# 14.net
KiCad netlist of a schematic drawn in EasyEDA Pro
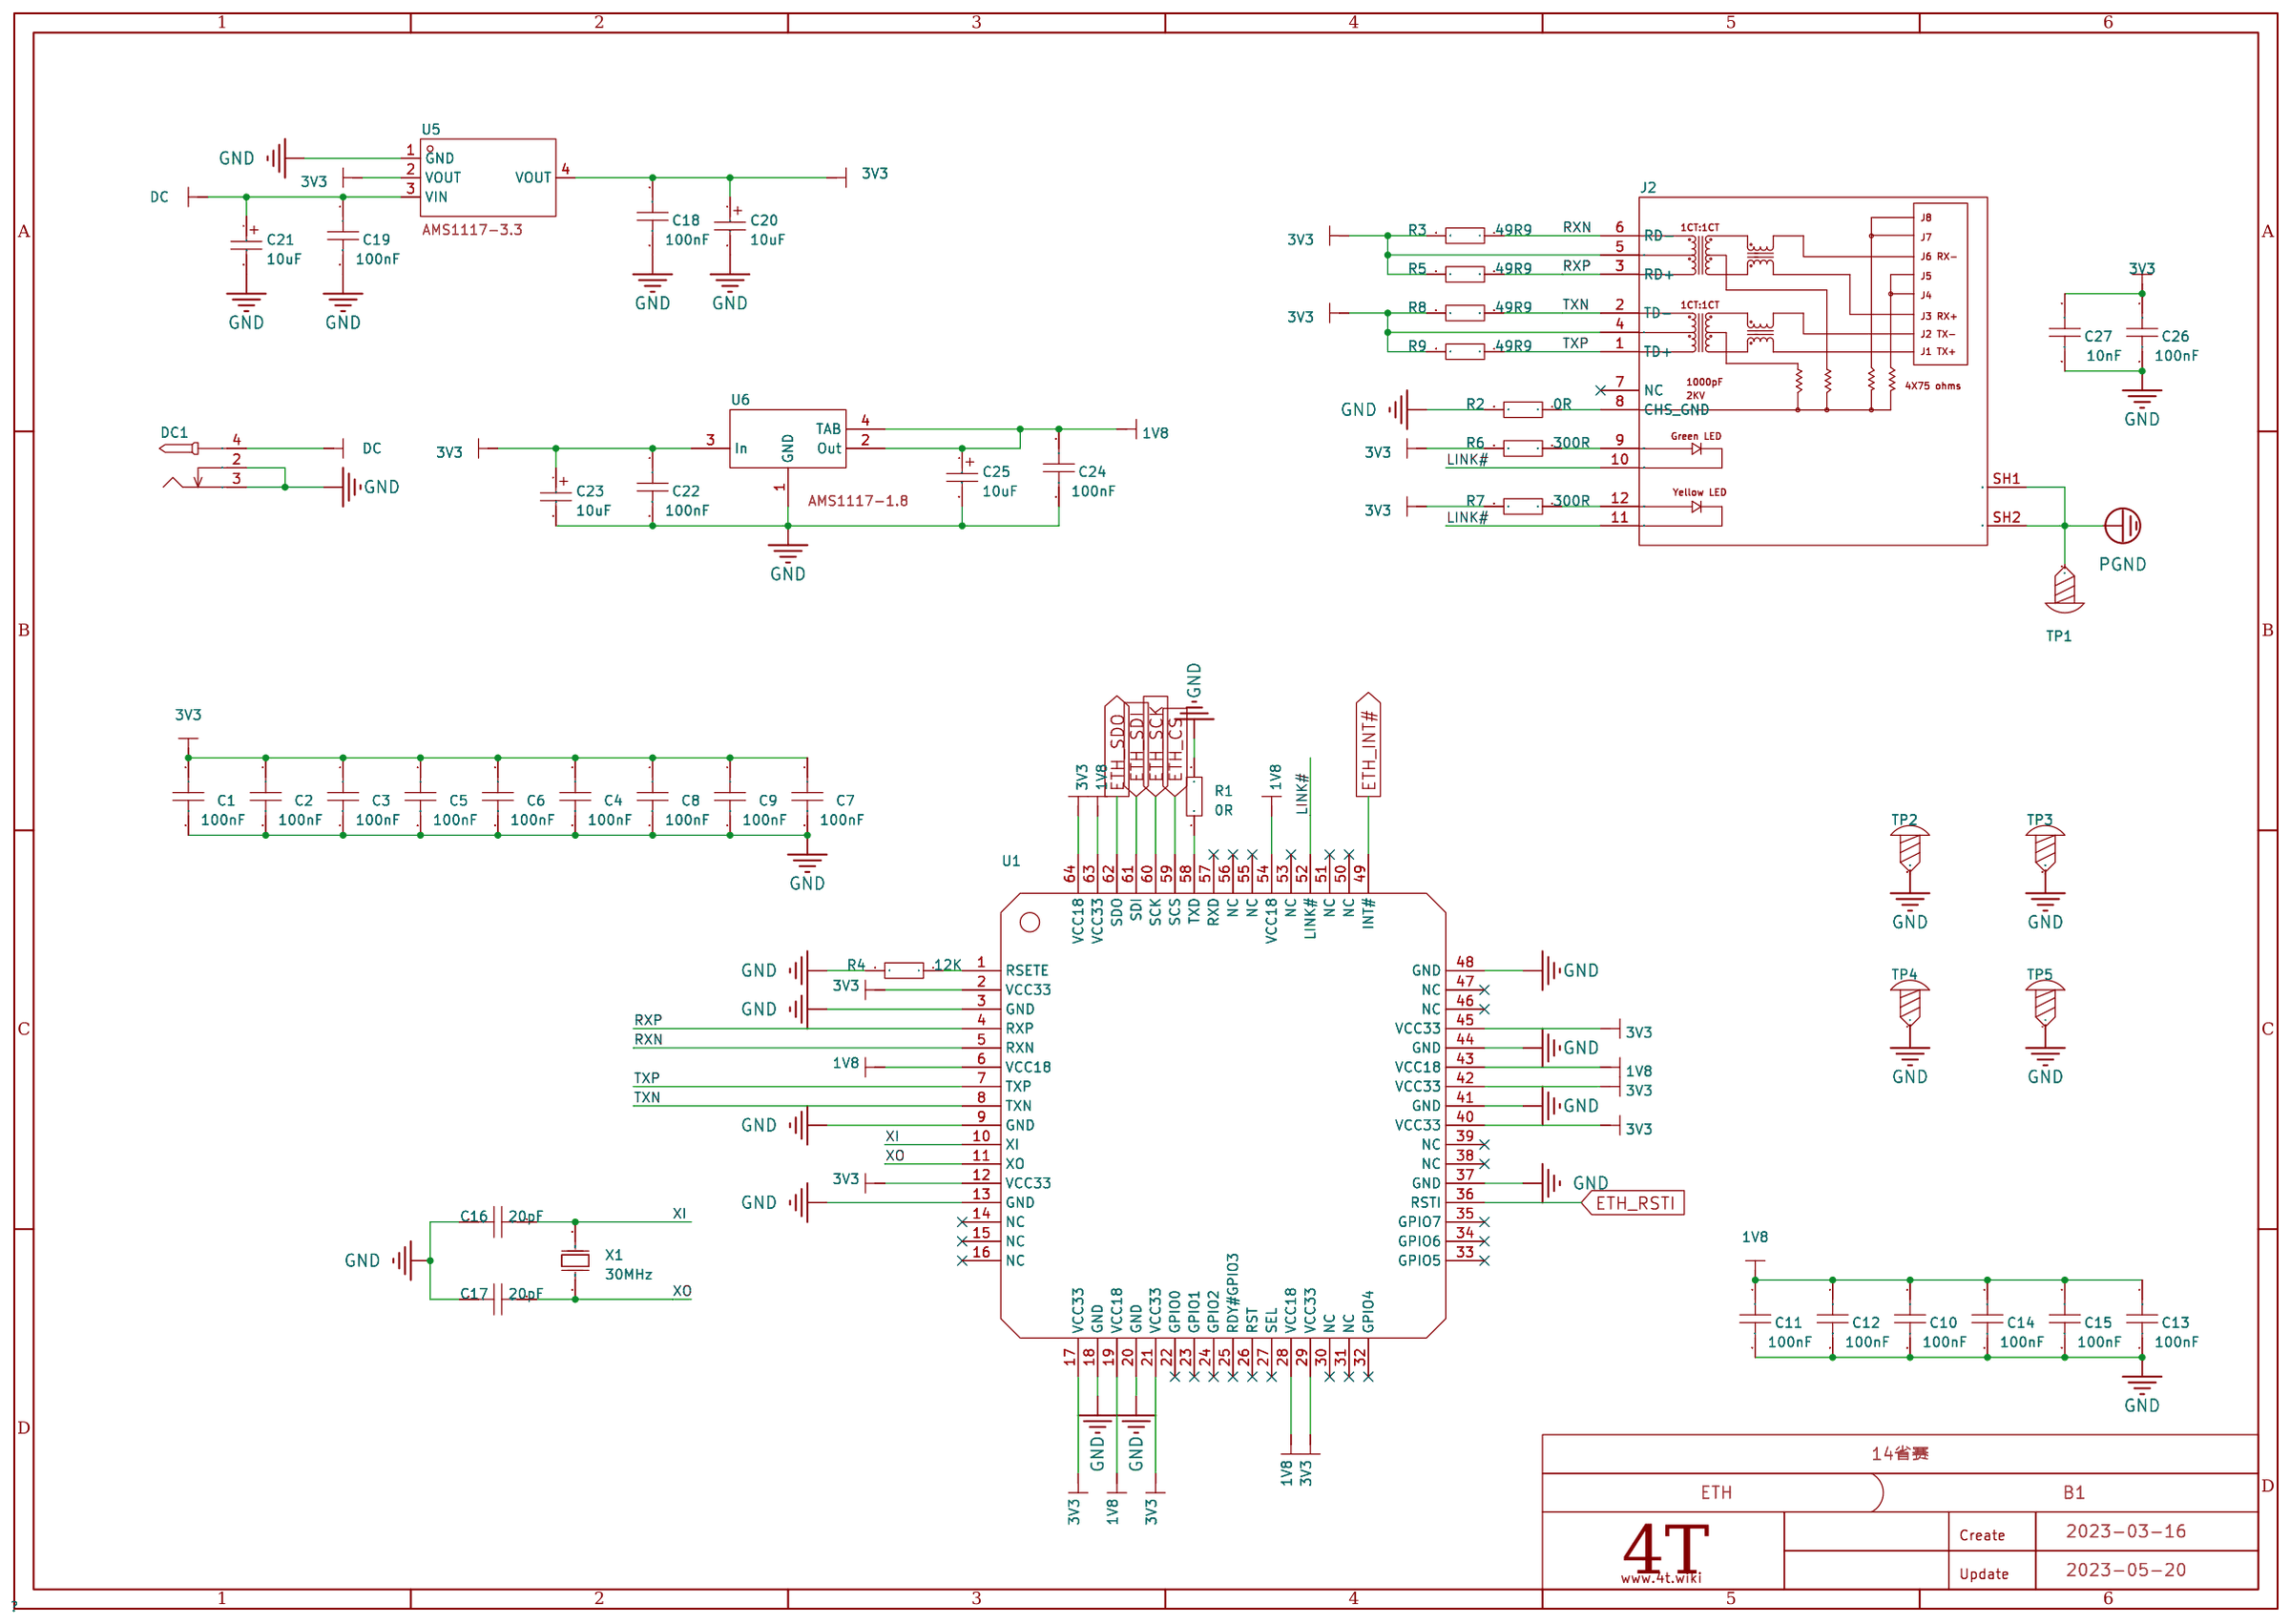
[diagram p0: ETH]
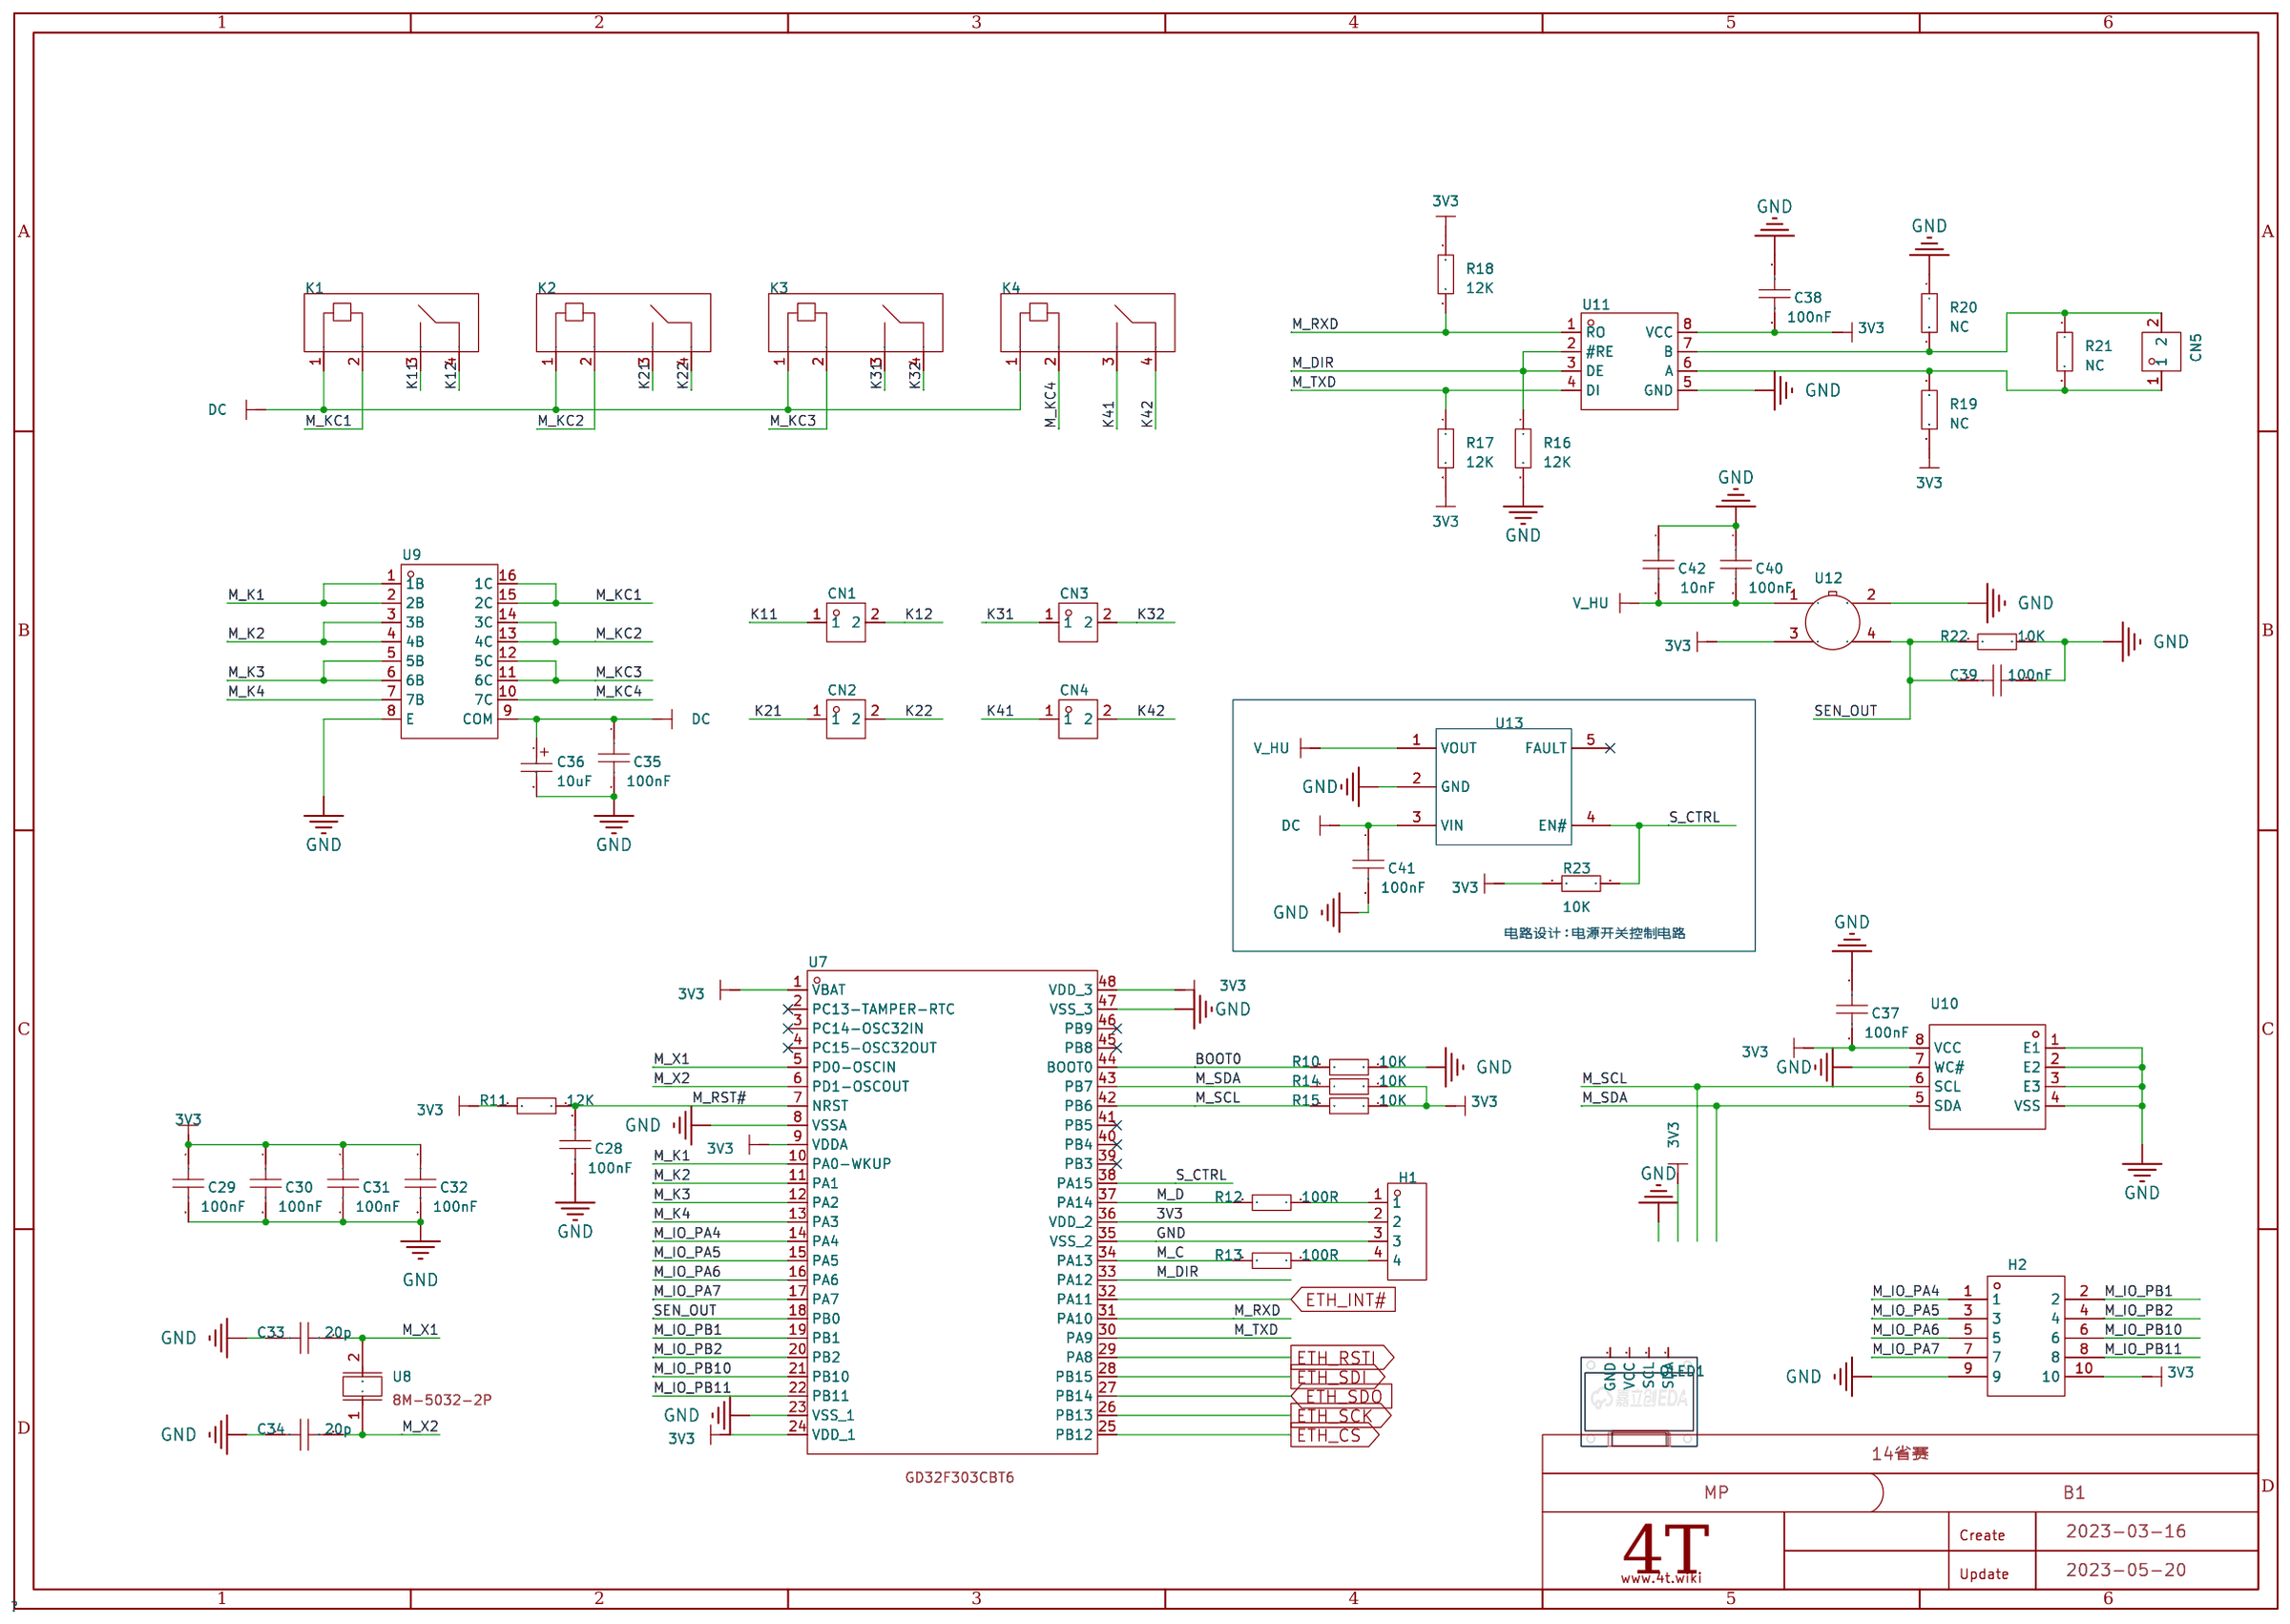
[diagram p1: MP]

(export (version "E")
  (design (tool "Eeschema 10.0.6"))
  (components
    (comp (ref "C1")
      (value "100nF")
      (footprint "easyedapro:C0805")
      (libsource (lib "easyedapro") (part "CapAcitance"))
    )
    (comp (ref "C2")
      (value "100nF")
      (footprint "easyedapro:C0805")
      (libsource (lib "easyedapro") (part "CapAcitance"))
    )
    (comp (ref "C3")
      (value "100nF")
      (footprint "easyedapro:C0805")
      (libsource (lib "easyedapro") (part "CapAcitance"))
    )
    (comp (ref "C4")
      (value "100nF")
      (footprint "easyedapro:C0805")
      (libsource (lib "easyedapro") (part "CapAcitance"))
    )
    (comp (ref "C5")
      (value "100nF")
      (footprint "easyedapro:C0805")
      (libsource (lib "easyedapro") (part "CapAcitance"))
    )
    (comp (ref "C6")
      (value "100nF")
      (footprint "easyedapro:C0805")
      (libsource (lib "easyedapro") (part "CapAcitance"))
    )
    (comp (ref "C7")
      (value "100nF")
      (footprint "easyedapro:C0805")
      (libsource (lib "easyedapro") (part "CapAcitance"))
    )
    (comp (ref "C8")
      (value "100nF")
      (footprint "easyedapro:C0805")
      (libsource (lib "easyedapro") (part "CapAcitance"))
    )
    (comp (ref "C9")
      (value "100nF")
      (footprint "easyedapro:C0805")
      (libsource (lib "easyedapro") (part "CapAcitance"))
    )
    (comp (ref "C10")
      (value "100nF")
      (footprint "easyedapro:C0805")
      (libsource (lib "easyedapro") (part "CapAcitance"))
    )
    (comp (ref "C11")
      (value "100nF")
      (footprint "easyedapro:C0805")
      (libsource (lib "easyedapro") (part "CapAcitance"))
    )
    (comp (ref "C12")
      (value "100nF")
      (footprint "easyedapro:C0805")
      (libsource (lib "easyedapro") (part "CapAcitance"))
    )
    (comp (ref "C13")
      (value "100nF")
      (footprint "easyedapro:C0805")
      (libsource (lib "easyedapro") (part "CapAcitance"))
    )
    (comp (ref "C14")
      (value "100nF")
      (footprint "easyedapro:C0805")
      (libsource (lib "easyedapro") (part "CapAcitance"))
    )
    (comp (ref "C15")
      (value "100nF")
      (footprint "easyedapro:C0805")
      (libsource (lib "easyedapro") (part "CapAcitance"))
    )
    (comp (ref "C16")
      (value "20pF")
      (footprint "easyedapro:C0805")
      (libsource (lib "easyedapro") (part "CapAcitance"))
    )
    (comp (ref "C17")
      (value "20pF")
      (footprint "easyedapro:C0805")
      (libsource (lib "easyedapro") (part "CapAcitance"))
    )
    (comp (ref "C18")
      (value "100nF")
      (footprint "easyedapro:C0805")
      (libsource (lib "easyedapro") (part "CapAcitance"))
    )
    (comp (ref "C19")
      (value "100nF")
      (footprint "easyedapro:C0805")
      (libsource (lib "easyedapro") (part "CapAcitance"))
    )
    (comp (ref "C20")
      (value "10uF")
      (footprint "easyedapro:C_Ele_SMD_3x5.4mm")
      (libsource (lib "easyedapro") (part "CAP"))
    )
    (comp (ref "C21")
      (value "10uF")
      (footprint "easyedapro:C_Ele_SMD_3x5.4mm")
      (libsource (lib "easyedapro") (part "CAP"))
    )
    (comp (ref "C22")
      (value "100nF")
      (footprint "easyedapro:C0805")
      (libsource (lib "easyedapro") (part "CapAcitance"))
    )
    (comp (ref "C23")
      (value "10uF")
      (footprint "easyedapro:C_Ele_SMD_3x5.4mm")
      (libsource (lib "easyedapro") (part "CAP"))
    )
    (comp (ref "C24")
      (value "100nF")
      (footprint "easyedapro:C0805")
      (libsource (lib "easyedapro") (part "CapAcitance"))
    )
    (comp (ref "C25")
      (value "10uF")
      (footprint "easyedapro:C_Ele_SMD_3x5.4mm")
      (libsource (lib "easyedapro") (part "CAP"))
    )
    (comp (ref "C26")
      (value "100nF")
      (footprint "easyedapro:C0805")
      (libsource (lib "easyedapro") (part "CapAcitance"))
    )
    (comp (ref "C27")
      (value "10nF")
      (footprint "easyedapro:C0805")
      (libsource (lib "easyedapro") (part "CapAcitance"))
    )
    (comp (ref "DC1")
      (value "~")
      (footprint "easyedapro:DC-2.0")
      (libsource (lib "easyedapro") (part "DC电源接口"))
    )
    (comp (ref "J2")
      (value "HY911105AE")
      (footprint "easyedapro:RJ45-TH_HR911105A")
      (description "连接器类型:RJ插座;USOC代码:RJ45;端口数量:1;等级:-;屏蔽:-;LED:-;")
      (fields (field (name "Manufacturer") "HANRUN(汉仁)"))
      (libsource (lib "easyedapro") (part "HY911105AE"))
    )
    (comp (ref "R1") (value "0R") (footprint "easyedapro:R0805") (libsource (lib "easyedapro") (part "电阻")))
    (comp (ref "R2") (value "0R") (footprint "easyedapro:R0805") (libsource (lib "easyedapro") (part "电阻")))
    (comp (ref "R3") (value "49R9") (footprint "easyedapro:R0805") (libsource (lib "easyedapro") (part "电阻")))
    (comp (ref "R4") (value "12K") (footprint "easyedapro:R0805") (libsource (lib "easyedapro") (part "电阻")))
    (comp (ref "R5") (value "49R9") (footprint "easyedapro:R0805") (libsource (lib "easyedapro") (part "电阻")))
    (comp (ref "R6") (value "300R") (footprint "easyedapro:R0805") (libsource (lib "easyedapro") (part "电阻")))
    (comp (ref "R7") (value "300R") (footprint "easyedapro:R0805") (libsource (lib "easyedapro") (part "电阻")))
    (comp (ref "R8") (value "49R9") (footprint "easyedapro:R0805") (libsource (lib "easyedapro") (part "电阻")))
    (comp (ref "R9") (value "49R9") (footprint "easyedapro:R0805") (libsource (lib "easyedapro") (part "电阻")))
    (comp (ref "TP1") (value "~") (footprint "easyedapro:M2螺丝") (libsource (lib "easyedapro") (part "螺丝孔")))
    (comp (ref "TP2") (value "~") (footprint "easyedapro:M2螺丝") (libsource (lib "easyedapro") (part "螺丝孔")))
    (comp (ref "TP3") (value "~") (footprint "easyedapro:M2螺丝") (libsource (lib "easyedapro") (part "螺丝孔")))
    (comp (ref "TP4") (value "~") (footprint "easyedapro:M2螺丝") (libsource (lib "easyedapro") (part "螺丝孔")))
    (comp (ref "TP5") (value "~") (footprint "easyedapro:M2螺丝") (libsource (lib "easyedapro") (part "螺丝孔")))
    (comp (ref "U1")
      (value "CH395Q")
      (footprint "easyedapro:LQFP-64_L10.0-W10.0-P0.50-LS12.0-BL")
      (description "应用功能:以太网控制器;通道数:-;接口类型:Parallel, SPI, UART;电源电压:1.65V~3.6V;电源电流:90mA;")
      (fields (field (name "Manufacturer") "WCH(南京沁恒)"))
      (libsource (lib "easyedapro") (part "CH395Q"))
    )
    (comp (ref "U5")
      (value "AMS1117-3.3")
      (footprint "easyedapro:SOT-223-3_L6.5-W3.4-P2.30-LS7.0-BR")
      (fields (field (name "Manufacturer Part") "AMS1117-3.3") (field (name "Manufacturer") "AMS"))
      (libsource (lib "easyedapro") (part "AMS1117-3.3"))
    )
    (comp (ref "U6")
      (value "AMS1117-1.8")
      (footprint "easyedapro:SOT-223-4_L6.5-W3.5-P2.30-LS7.0-BR")
      (description "输出类型:固定;输出极性:正;输出通道数:1;最大输入电压:15V;输出电压:1.8V~1.8V;压差:1.3V@(1A);输出电流:1A;电源纹波抑制比(PSRR):75dB@(120Hz);")
      (fields (field (name "Manufacturer Part") "AMS1117-1.8") (field (name "Manufacturer") "AMS"))
      (libsource (lib "easyedapro") (part "AMS1117-1.8"))
    )
    (comp (ref "X1")
      (value "30MHz")
      (footprint "easyedapro:OSC-SMD_L5.0-W3.2")
      (description "晶振类型:贴片无源晶振;频率:30MHz;频率公差:±10ppm;频率稳定度:±50ppm;负载电容:20pF;工作温度:-40°C~+85°C;")
      (fields (field (name "Manufacturer Part") "X503230MSB2GI") (field (name "Manufacturer") "YXC(扬兴晶振)"))
      (libsource (lib "easyedapro") (part "X503230MSB2GI"))
    )
    (comp (ref "C28")
      (value "100nF")
      (footprint "easyedapro:C0805")
      (libsource (lib "easyedapro") (part "CapAcitance"))
    )
    (comp (ref "C29")
      (value "100nF")
      (footprint "easyedapro:C0805")
      (libsource (lib "easyedapro") (part "CapAcitance"))
    )
    (comp (ref "C30")
      (value "100nF")
      (footprint "easyedapro:C0805")
      (libsource (lib "easyedapro") (part "CapAcitance"))
    )
    (comp (ref "C31")
      (value "100nF")
      (footprint "easyedapro:C0805")
      (libsource (lib "easyedapro") (part "CapAcitance"))
    )
    (comp (ref "C32")
      (value "100nF")
      (footprint "easyedapro:C0805")
      (libsource (lib "easyedapro") (part "CapAcitance"))
    )
    (comp (ref "C33")
      (value "20p")
      (footprint "easyedapro:C0805")
      (libsource (lib "easyedapro") (part "CapAcitance"))
    )
    (comp (ref "C34")
      (value "20p")
      (footprint "easyedapro:C0805")
      (libsource (lib "easyedapro") (part "CapAcitance"))
    )
    (comp (ref "C35")
      (value "100nF")
      (footprint "easyedapro:C0805")
      (libsource (lib "easyedapro") (part "CapAcitance"))
    )
    (comp (ref "C36")
      (value "10uF")
      (footprint "easyedapro:C_Ele_SMD_3x5.4mm")
      (libsource (lib "easyedapro") (part "CAP"))
    )
    (comp (ref "C37")
      (value "100nF")
      (footprint "easyedapro:C0805")
      (libsource (lib "easyedapro") (part "CapAcitance"))
    )
    (comp (ref "C38")
      (value "100nF")
      (footprint "easyedapro:C0805")
      (libsource (lib "easyedapro") (part "CapAcitance"))
    )
    (comp (ref "C39")
      (value "100nF")
      (footprint "easyedapro:C0805")
      (libsource (lib "easyedapro") (part "CapAcitance"))
    )
    (comp (ref "C40")
      (value "100nF")
      (footprint "easyedapro:C0805")
      (libsource (lib "easyedapro") (part "CapAcitance"))
    )
    (comp (ref "C41")
      (value "100nF")
      (footprint "easyedapro:C0805")
      (libsource (lib "easyedapro") (part "CapAcitance"))
    )
    (comp (ref "C42")
      (value "10nF")
      (footprint "easyedapro:C0805")
      (libsource (lib "easyedapro") (part "CapAcitance"))
    )
    (comp (ref "CN1")
      (value "KF128L-5.08-2P 蓝色")
      (footprint "easyedapro:TH_KF128L-5.08-2P")
      (libsource (lib "easyedapro") (part "KF128L-5.08-2P 蓝色"))
    )
    (comp (ref "CN2")
      (value "KF128L-5.08-2P 蓝色")
      (footprint "easyedapro:TH_KF128L-5.08-2P")
      (libsource (lib "easyedapro") (part "KF128L-5.08-2P 蓝色"))
    )
    (comp (ref "CN3")
      (value "KF128L-5.08-2P 蓝色")
      (footprint "easyedapro:TH_KF128L-5.08-2P")
      (libsource (lib "easyedapro") (part "KF128L-5.08-2P 蓝色"))
    )
    (comp (ref "CN4")
      (value "KF128L-5.08-2P 蓝色")
      (footprint "easyedapro:TH_KF128L-5.08-2P")
      (libsource (lib "easyedapro") (part "KF128L-5.08-2P 蓝色"))
    )
    (comp (ref "CN5")
      (value "KF128L-5.08-2P 蓝色")
      (footprint "easyedapro:TH_KF128L-5.08-2P")
      (libsource (lib "easyedapro") (part "KF128L-5.08-2P 蓝色"))
    )
    (comp (ref "H1")
      (value "~")
      (footprint "easyedapro:HDR-TH_4P-P2.54-V-F")
      (libsource (lib "easyedapro") (part "2.54-1*4P母"))
    )
    (comp (ref "H2")
      (value "~")
      (footprint "easyedapro:HDR-TH_10P-P2.54-V-M-R2-C5-S2.54")
      (libsource (lib "easyedapro") (part "HDR-M-2.54_2x5"))
    )
    (comp (ref "K1")
      (value "HF49FD/012-1H12")
      (footprint "easyedapro:RELAY-TH_HF49FD-XXX-1H12-XXX")
      (description "线圈电压:12V;线圈类型:非极化-单线圈;触点形式:一组常开:1A(单刀单掷-常开);最大切换电流:5A;触点材料:AgNi;")
      (fields (field (name "Manufacturer") "HF(宏发)"))
      (libsource (lib "easyedapro") (part "HF49FD/012-1H12"))
    )
    (comp (ref "K2")
      (value "HF49FD/012-1H12")
      (footprint "easyedapro:RELAY-TH_HF49FD-XXX-1H12-XXX")
      (description "线圈电压:12V;线圈类型:非极化-单线圈;触点形式:一组常开:1A(单刀单掷-常开);最大切换电流:5A;触点材料:AgNi;")
      (fields (field (name "Manufacturer") "HF(宏发)"))
      (libsource (lib "easyedapro") (part "HF49FD/012-1H12"))
    )
    (comp (ref "K3")
      (value "HF49FD/012-1H12")
      (footprint "easyedapro:RELAY-TH_HF49FD-XXX-1H12-XXX")
      (description "线圈电压:12V;线圈类型:非极化-单线圈;触点形式:一组常开:1A(单刀单掷-常开);最大切换电流:5A;触点材料:AgNi;")
      (fields (field (name "Manufacturer") "HF(宏发)"))
      (libsource (lib "easyedapro") (part "HF49FD/012-1H12"))
    )
    (comp (ref "K4")
      (value "HF49FD/012-1H12")
      (footprint "easyedapro:RELAY-TH_HF49FD-XXX-1H12-XXX")
      (description "线圈电压:12V;线圈类型:非极化-单线圈;触点形式:一组常开:1A(单刀单掷-常开);最大切换电流:5A;触点材料:AgNi;")
      (fields (field (name "Manufacturer") "HF(宏发)"))
      (libsource (lib "easyedapro") (part "HF49FD/012-1H12"))
    )
    (comp (ref "OLED1")
      (value "~")
      (footprint "easyedapro:0.96OLED_4P")
      (libsource (lib "easyedapro") (part "0.96OLED模块_4P"))
    )
    (comp (ref "R10") (value "10K") (footprint "easyedapro:R0805") (libsource (lib "easyedapro") (part "电阻")))
    (comp (ref "R11") (value "12K") (footprint "easyedapro:R0805") (libsource (lib "easyedapro") (part "电阻")))
    (comp (ref "R12")
      (value "100R")
      (footprint "easyedapro:R0805")
      (libsource (lib "easyedapro") (part "电阻"))
    )
    (comp (ref "R13")
      (value "100R")
      (footprint "easyedapro:R0805")
      (libsource (lib "easyedapro") (part "电阻"))
    )
    (comp (ref "R14") (value "10K") (footprint "easyedapro:R0805") (libsource (lib "easyedapro") (part "电阻")))
    (comp (ref "R15") (value "10K") (footprint "easyedapro:R0805") (libsource (lib "easyedapro") (part "电阻")))
    (comp (ref "R16") (value "12K") (footprint "easyedapro:R0805") (libsource (lib "easyedapro") (part "电阻")))
    (comp (ref "R17") (value "12K") (footprint "easyedapro:R0805") (libsource (lib "easyedapro") (part "电阻")))
    (comp (ref "R18") (value "12K") (footprint "easyedapro:R0805") (libsource (lib "easyedapro") (part "电阻")))
    (comp (ref "R19") (value "NC") (footprint "easyedapro:R0805") (libsource (lib "easyedapro") (part "电阻")))
    (comp (ref "R20") (value "NC") (footprint "easyedapro:R0805") (libsource (lib "easyedapro") (part "电阻")))
    (comp (ref "R21") (value "NC") (footprint "easyedapro:R0805") (libsource (lib "easyedapro") (part "电阻")))
    (comp (ref "R22") (value "10K") (footprint "easyedapro:R0805") (libsource (lib "easyedapro") (part "电阻")))
    (comp (ref "R23") (value "10K") (footprint "easyedapro:R0805") (libsource (lib "easyedapro") (part "电阻")))
    (comp (ref "U7")
      (value "GD32F303CBT6")
      (footprint "easyedapro:LQFP-48_L7.0-W7.0-P0.50-LS9.0-BL")
      (fields
        (field (name "Manufacturer Part") "GD32F303CBT6")
        (field (name "Manufacturer") "GigaDevice(兆易创新)")
      )
      (libsource (lib "easyedapro") (part "GD32F303CBT6"))
    )
    (comp (ref "U8")
      (value "8M-5032-2P")
      (footprint "easyedapro:CRYSTAL-SMD_L5.0-W3.2")
      (fields (field (name "Manufacturer Part") "8M-5032-2P"))
      (libsource (lib "easyedapro") (part "8M-5032-2P"))
    )
    (comp (ref "U9")
      (value "ULN2003")
      (footprint "easyedapro:SOIC-16_L9.9-W3.9-P1.27-LS6.0-BL")
      (fields (field (name "Manufacturer") "IDCHIP(英锐芯)"))
      (libsource (lib "easyedapro") (part "ULN2003_C688859"))
    )
    (comp (ref "U10")
      (value "M24C02-WMN6TP")
      (footprint "easyedapro:SOIC-8_L4.9-W3.9-P1.27-LS6.0-BL")
      (description "2-Kbit(256 x 8bit)，I2C接口，工作电压：2.5V to 5.5V")
      (fields (field (name "Manufacturer") "ST(意法半导体)"))
      (libsource (lib "easyedapro") (part "M24C02-WMN6TP"))
    )
    (comp (ref "U11")
      (value "MAX3485ESA")
      (footprint "easyedapro:SOP-8_L5.0-W4.0-P1.27-LS6.0-BL")
      (fields (field (name "Manufacturer") "UMW(广东友台半导体)"))
      (libsource (lib "easyedapro") (part "MAX3485ESA"))
    )
    (comp (ref "U12")
      (value "MP-2")
      (footprint "easyedapro:SENSOR-TH_MP-5")
      (fields (field (name "Manufacturer") "Winsen(炜盛)"))
      (libsource (lib "easyedapro") (part "MP-2"))
    )
    (comp (ref "U13") (value "~") (libsource (lib "easyedapro") (part "PDS")))
  )
  (nets
    (net (code "1") (name "1V8") (class "Default")
      (node (ref "C10") (pin "1") (pinfunction "1_1") (pintype "input"))
      (node (ref "C11") (pin "1") (pinfunction "1_1") (pintype "input"))
      (node (ref "C12") (pin "1") (pinfunction "1_1") (pintype "input"))
      (node (ref "C13") (pin "1") (pinfunction "1_1") (pintype "input"))
      (node (ref "C14") (pin "1") (pinfunction "1_1") (pintype "input"))
      (node (ref "C15") (pin "1") (pinfunction "1_1") (pintype "input"))
      (node (ref "C24") (pin "1") (pinfunction "1_1") (pintype "input"))
      (node (ref "C25") (pin "1") (pinfunction "1_1") (pintype "input"))
      (node (ref "U1") (pin "19") (pinfunction "VCC18_19") (pintype "input"))
      (node (ref "U1") (pin "28") (pinfunction "VCC18_28") (pintype "input"))
      (node (ref "U1") (pin "43") (pinfunction "VCC18_43") (pintype "input"))
      (node (ref "U1") (pin "54") (pinfunction "VCC18_54") (pintype "input"))
      (node (ref "U1") (pin "6") (pinfunction "VCC18_6") (pintype "input"))
      (node (ref "U1") (pin "63") (pinfunction "VCC33_63") (pintype "input"))
      (node (ref "U6") (pin "2") (pinfunction "Out_2") (pintype "input"))
      (node (ref "U6") (pin "4") (pinfunction "TAB_4") (pintype "input"))
    )
    (net (code "2") (name "3V3") (class "Default")
      (node (ref "C1") (pin "1") (pinfunction "1_1") (pintype "input"))
      (node (ref "C18") (pin "1") (pinfunction "1_1") (pintype "input"))
      (node (ref "C2") (pin "1") (pinfunction "1_1") (pintype "input"))
      (node (ref "C20") (pin "1") (pinfunction "1_1") (pintype "input"))
      (node (ref "C22") (pin "1") (pinfunction "1_1") (pintype "input"))
      (node (ref "C23") (pin "1") (pinfunction "1_1") (pintype "input"))
      (node (ref "C26") (pin "1") (pinfunction "1_1") (pintype "input"))
      (node (ref "C27") (pin "1") (pinfunction "1_1") (pintype "input"))
      (node (ref "C29") (pin "1") (pinfunction "1_1") (pintype "input"))
      (node (ref "C3") (pin "1") (pinfunction "1_1") (pintype "input"))
      (node (ref "C30") (pin "1") (pinfunction "1_1") (pintype "input"))
      (node (ref "C31") (pin "1") (pinfunction "1_1") (pintype "input"))
      (node (ref "C32") (pin "1") (pinfunction "1_1") (pintype "input"))
      (node (ref "C37") (pin "2") (pinfunction "2_2") (pintype "input"))
      (node (ref "C38") (pin "2") (pinfunction "2_2") (pintype "input"))
      (node (ref "C4") (pin "1") (pinfunction "1_1") (pintype "input"))
      (node (ref "C5") (pin "1") (pinfunction "1_1") (pintype "input"))
      (node (ref "C6") (pin "1") (pinfunction "1_1") (pintype "input"))
      (node (ref "C7") (pin "1") (pinfunction "1_1") (pintype "input"))
      (node (ref "C8") (pin "1") (pinfunction "1_1") (pintype "input"))
      (node (ref "C9") (pin "1") (pinfunction "1_1") (pintype "input"))
      (node (ref "H1") (pin "2") (pinfunction "2_2") (pintype "input"))
      (node (ref "H2") (pin "10") (pinfunction "10_10") (pintype "input"))
      (node (ref "J2") (pin "4") (pinfunction "4_4") (pintype "input"))
      (node (ref "J2") (pin "5") (pinfunction "5_5") (pintype "input"))
      (node (ref "R11") (pin "2") (pinfunction "2_2") (pintype "input"))
      (node (ref "R14") (pin "2") (pinfunction "2_2") (pintype "input"))
      (node (ref "R15") (pin "1") (pinfunction "1_1") (pintype "input"))
      (node (ref "R17") (pin "2") (pinfunction "2_2") (pintype "input"))
      (node (ref "R18") (pin "1") (pinfunction "1_1") (pintype "input"))
      (node (ref "R19") (pin "2") (pinfunction "2_2") (pintype "input"))
      (node (ref "R23") (pin "1") (pinfunction "1_1") (pintype "input"))
      (node (ref "R3") (pin "2") (pinfunction "2_2") (pintype "input"))
      (node (ref "R5") (pin "2") (pinfunction "2_2") (pintype "input"))
      (node (ref "R6") (pin "2") (pinfunction "2_2") (pintype "input"))
      (node (ref "R7") (pin "2") (pinfunction "2_2") (pintype "input"))
      (node (ref "R8") (pin "2") (pinfunction "2_2") (pintype "input"))
      (node (ref "R9") (pin "2") (pinfunction "2_2") (pintype "input"))
      (node (ref "U1") (pin "12") (pinfunction "VCC33_12") (pintype "input"))
      (node (ref "U1") (pin "17") (pinfunction "VCC33_17") (pintype "input"))
      (node (ref "U1") (pin "2") (pinfunction "VCC33_2") (pintype "input"))
      (node (ref "U1") (pin "21") (pinfunction "VCC33_21") (pintype "input"))
      (node (ref "U1") (pin "29") (pinfunction "VCC33_29") (pintype "input"))
      (node (ref "U1") (pin "40") (pinfunction "VCC33_40") (pintype "input"))
      (node (ref "U1") (pin "42") (pinfunction "VCC33_42") (pintype "input"))
      (node (ref "U1") (pin "45") (pinfunction "VCC33_45") (pintype "input"))
      (node (ref "U1") (pin "64") (pinfunction "VCC18_64") (pintype "input"))
      (node (ref "U10") (pin "8") (pinfunction "VCC_8") (pintype "input"))
      (node (ref "U11") (pin "8") (pinfunction "VCC_8") (pintype "input"))
      (node (ref "U12") (pin "3") (pinfunction "3_3") (pintype "input"))
      (node (ref "U5") (pin "2") (pinfunction "VOUT_2") (pintype "input"))
      (node (ref "U5") (pin "4") (pinfunction "VOUT_4") (pintype "input"))
      (node (ref "U6") (pin "3") (pinfunction "In_3") (pintype "input"))
      (node (ref "U7") (pin "1") (pinfunction "VBAT_1") (pintype "input"))
      (node (ref "U7") (pin "24") (pinfunction "VDD_1_24") (pintype "input"))
      (node (ref "U7") (pin "36") (pinfunction "VDD_2_36") (pintype "input"))
      (node (ref "U7") (pin "48") (pinfunction "VDD_3_48") (pintype "input"))
      (node (ref "U7") (pin "9") (pinfunction "VDDA_9") (pintype "input"))
    )
    (net (code "3") (name "BOOT0") (class "Default")
      (node (ref "R10") (pin "2") (pinfunction "2_2") (pintype "input"))
      (node (ref "U7") (pin "44") (pinfunction "BOOT0_44") (pintype "input"))
    )
    (net (code "4") (name "DC") (class "Default")
      (node (ref "C19") (pin "1") (pinfunction "1_1") (pintype "input"))
      (node (ref "C21") (pin "1") (pinfunction "1_1") (pintype "input"))
      (node (ref "C35") (pin "1") (pinfunction "1_1") (pintype "input"))
      (node (ref "C36") (pin "1") (pinfunction "1_1") (pintype "input"))
      (node (ref "C41") (pin "1") (pinfunction "1_1") (pintype "input"))
      (node (ref "DC1") (pin "4") (pinfunction "4_4") (pintype "input"))
      (node (ref "K1") (pin "1") (pinfunction "1_1") (pintype "input"))
      (node (ref "K2") (pin "1") (pinfunction "1_1") (pintype "input"))
      (node (ref "K3") (pin "1") (pinfunction "1_1") (pintype "input"))
      (node (ref "K4") (pin "1") (pinfunction "1_1") (pintype "input"))
      (node (ref "U13") (pin "3") (pinfunction "VIN_3") (pintype "input"))
      (node (ref "U5") (pin "3") (pinfunction "VIN_3") (pintype "input"))
      (node (ref "U9") (pin "9") (pinfunction "COM_9") (pintype "input"))
    )
    (net (code "5") (name "ETH_CS") (class "Default")
      (node (ref "U1") (pin "59") (pinfunction "SCS_59") (pintype "input"))
      (node (ref "U7") (pin "25") (pinfunction "PB12_25") (pintype "input"))
    )
    (net (code "6") (name "ETH_INT#") (class "Default")
      (node (ref "U1") (pin "49") (pinfunction "INT#_49") (pintype "input"))
      (node (ref "U7") (pin "32") (pinfunction "PA11_32") (pintype "input"))
    )
    (net (code "7") (name "ETH_RSTI") (class "Default")
      (node (ref "U1") (pin "36") (pinfunction "RSTI_36") (pintype "input"))
      (node (ref "U7") (pin "29") (pinfunction "PA8_29") (pintype "input"))
    )
    (net (code "8") (name "ETH_SCK") (class "Default")
      (node (ref "U1") (pin "60") (pinfunction "SCK_60") (pintype "input"))
      (node (ref "U7") (pin "26") (pinfunction "PB13_26") (pintype "input"))
    )
    (net (code "9") (name "ETH_SDI") (class "Default")
      (node (ref "U1") (pin "61") (pinfunction "SDI_61") (pintype "input"))
      (node (ref "U7") (pin "28") (pinfunction "PB15_28") (pintype "input"))
    )
    (net (code "10") (name "ETH_SDO") (class "Default")
      (node (ref "U1") (pin "62") (pinfunction "SDO_62") (pintype "input"))
      (node (ref "U7") (pin "27") (pinfunction "PB14_27") (pintype "input"))
    )
    (net (code "11") (name "GND") (class "Default")
      (node (ref "C1") (pin "2") (pinfunction "2_2") (pintype "input"))
      (node (ref "C10") (pin "2") (pinfunction "2_2") (pintype "input"))
      (node (ref "C11") (pin "2") (pinfunction "2_2") (pintype "input"))
      (node (ref "C12") (pin "2") (pinfunction "2_2") (pintype "input"))
      (node (ref "C13") (pin "2") (pinfunction "2_2") (pintype "input"))
      (node (ref "C14") (pin "2") (pinfunction "2_2") (pintype "input"))
      (node (ref "C15") (pin "2") (pinfunction "2_2") (pintype "input"))
      (node (ref "C16") (pin "1") (pinfunction "1_1") (pintype "input"))
      (node (ref "C17") (pin "1") (pinfunction "1_1") (pintype "input"))
      (node (ref "C18") (pin "2") (pinfunction "2_2") (pintype "input"))
      (node (ref "C19") (pin "2") (pinfunction "2_2") (pintype "input"))
      (node (ref "C2") (pin "2") (pinfunction "2_2") (pintype "input"))
      (node (ref "C20") (pin "2") (pinfunction "2_2") (pintype "input"))
      (node (ref "C21") (pin "2") (pinfunction "2_2") (pintype "input"))
      (node (ref "C22") (pin "2") (pinfunction "2_2") (pintype "input"))
      (node (ref "C23") (pin "2") (pinfunction "2_2") (pintype "input"))
      (node (ref "C24") (pin "2") (pinfunction "2_2") (pintype "input"))
      (node (ref "C25") (pin "2") (pinfunction "2_2") (pintype "input"))
      (node (ref "C26") (pin "2") (pinfunction "2_2") (pintype "input"))
      (node (ref "C27") (pin "2") (pinfunction "2_2") (pintype "input"))
      (node (ref "C28") (pin "2") (pinfunction "2_2") (pintype "input"))
      (node (ref "C29") (pin "2") (pinfunction "2_2") (pintype "input"))
      (node (ref "C3") (pin "2") (pinfunction "2_2") (pintype "input"))
      (node (ref "C30") (pin "2") (pinfunction "2_2") (pintype "input"))
      (node (ref "C31") (pin "2") (pinfunction "2_2") (pintype "input"))
      (node (ref "C32") (pin "2") (pinfunction "2_2") (pintype "input"))
      (node (ref "C33") (pin "1") (pinfunction "1_1") (pintype "input"))
      (node (ref "C34") (pin "1") (pinfunction "1_1") (pintype "input"))
      (node (ref "C35") (pin "2") (pinfunction "2_2") (pintype "input"))
      (node (ref "C36") (pin "2") (pinfunction "2_2") (pintype "input"))
      (node (ref "C37") (pin "1") (pinfunction "1_1") (pintype "input"))
      (node (ref "C38") (pin "1") (pinfunction "1_1") (pintype "input"))
      (node (ref "C39") (pin "2") (pinfunction "2_2") (pintype "input"))
      (node (ref "C4") (pin "2") (pinfunction "2_2") (pintype "input"))
      (node (ref "C40") (pin "1") (pinfunction "1_1") (pintype "input"))
      (node (ref "C41") (pin "2") (pinfunction "2_2") (pintype "input"))
      (node (ref "C42") (pin "1") (pinfunction "1_1") (pintype "input"))
      (node (ref "C5") (pin "2") (pinfunction "2_2") (pintype "input"))
      (node (ref "C6") (pin "2") (pinfunction "2_2") (pintype "input"))
      (node (ref "C7") (pin "2") (pinfunction "2_2") (pintype "input"))
      (node (ref "C8") (pin "2") (pinfunction "2_2") (pintype "input"))
      (node (ref "C9") (pin "2") (pinfunction "2_2") (pintype "input"))
      (node (ref "DC1") (pin "2") (pinfunction "2_2") (pintype "input"))
      (node (ref "DC1") (pin "3") (pinfunction "3_3") (pintype "input"))
      (node (ref "H1") (pin "3") (pinfunction "3_3") (pintype "input"))
      (node (ref "H2") (pin "9") (pinfunction "9_9") (pintype "input"))
      (node (ref "R1") (pin "2") (pinfunction "2_2") (pintype "input"))
      (node (ref "R10") (pin "1") (pinfunction "1_1") (pintype "input"))
      (node (ref "R16") (pin "2") (pinfunction "2_2") (pintype "input"))
      (node (ref "R2") (pin "2") (pinfunction "2_2") (pintype "input"))
      (node (ref "R20") (pin "1") (pinfunction "1_1") (pintype "input"))
      (node (ref "R22") (pin "2") (pinfunction "2_2") (pintype "input"))
      (node (ref "R4") (pin "2") (pinfunction "2_2") (pintype "input"))
      (node (ref "TP2") (pin "1") (pinfunction "1_1") (pintype "input"))
      (node (ref "TP3") (pin "1") (pinfunction "1_1") (pintype "input"))
      (node (ref "TP4") (pin "1") (pinfunction "1_1") (pintype "input"))
      (node (ref "TP5") (pin "1") (pinfunction "1_1") (pintype "input"))
      (node (ref "U1") (pin "13") (pinfunction "GND_13") (pintype "input"))
      (node (ref "U1") (pin "18") (pinfunction "GND_18") (pintype "input"))
      (node (ref "U1") (pin "20") (pinfunction "GND_20") (pintype "input"))
      (node (ref "U1") (pin "3") (pinfunction "GND_3") (pintype "input"))
      (node (ref "U1") (pin "37") (pinfunction "GND_37") (pintype "input"))
      (node (ref "U1") (pin "41") (pinfunction "GND_41") (pintype "input"))
      (node (ref "U1") (pin "44") (pinfunction "GND_44") (pintype "input"))
      (node (ref "U1") (pin "48") (pinfunction "GND_48") (pintype "input"))
      (node (ref "U1") (pin "9") (pinfunction "GND_9") (pintype "input"))
      (node (ref "U10") (pin "1") (pinfunction "E1_1") (pintype "input"))
      (node (ref "U10") (pin "2") (pinfunction "E2_2") (pintype "input"))
      (node (ref "U10") (pin "3") (pinfunction "E3_3") (pintype "input"))
      (node (ref "U10") (pin "4") (pinfunction "VSS_4") (pintype "input"))
      (node (ref "U10") (pin "7") (pinfunction "WC#_7") (pintype "input"))
      (node (ref "U11") (pin "5") (pinfunction "GND_5") (pintype "input"))
      (node (ref "U12") (pin "2") (pinfunction "2_2") (pintype "input"))
      (node (ref "U13") (pin "2") (pinfunction "GND_2") (pintype "input"))
      (node (ref "U5") (pin "1") (pinfunction "GND_1") (pintype "input"))
      (node (ref "U6") (pin "1") (pinfunction "GND_1") (pintype "input"))
      (node (ref "U7") (pin "23") (pinfunction "VSS_1_23") (pintype "input"))
      (node (ref "U7") (pin "35") (pinfunction "VSS_2_35") (pintype "input"))
      (node (ref "U7") (pin "47") (pinfunction "VSS_3_47") (pintype "input"))
      (node (ref "U7") (pin "8") (pinfunction "VSSA_8") (pintype "input"))
      (node (ref "U9") (pin "8") (pinfunction "E_8") (pintype "input"))
    )
    (net (code "12") (name "K11") (class "Default")
      (node (ref "CN1") (pin "1") (pinfunction "1_1") (pintype "input"))
      (node (ref "K1") (pin "3") (pinfunction "3_3") (pintype "input"))
    )
    (net (code "13") (name "K12") (class "Default")
      (node (ref "CN1") (pin "2") (pinfunction "2_2") (pintype "input"))
      (node (ref "K1") (pin "4") (pinfunction "4_4") (pintype "input"))
    )
    (net (code "14") (name "K21") (class "Default")
      (node (ref "CN2") (pin "1") (pinfunction "1_1") (pintype "input"))
      (node (ref "K2") (pin "3") (pinfunction "3_3") (pintype "input"))
    )
    (net (code "15") (name "K22") (class "Default")
      (node (ref "CN2") (pin "2") (pinfunction "2_2") (pintype "input"))
      (node (ref "K2") (pin "4") (pinfunction "4_4") (pintype "input"))
    )
    (net (code "16") (name "K31") (class "Default")
      (node (ref "CN3") (pin "1") (pinfunction "1_1") (pintype "input"))
      (node (ref "K3") (pin "3") (pinfunction "3_3") (pintype "input"))
    )
    (net (code "17") (name "K32") (class "Default")
      (node (ref "CN3") (pin "2") (pinfunction "2_2") (pintype "input"))
      (node (ref "K3") (pin "4") (pinfunction "4_4") (pintype "input"))
    )
    (net (code "18") (name "K41") (class "Default")
      (node (ref "CN4") (pin "1") (pinfunction "1_1") (pintype "input"))
      (node (ref "K4") (pin "3") (pinfunction "3_3") (pintype "input"))
    )
    (net (code "19") (name "K42") (class "Default")
      (node (ref "CN4") (pin "2") (pinfunction "2_2") (pintype "input"))
      (node (ref "K4") (pin "4") (pinfunction "4_4") (pintype "input"))
    )
    (net (code "20") (name "LINK#") (class "Default")
      (node (ref "J2") (pin "10") (pinfunction "10_10") (pintype "input"))
      (node (ref "J2") (pin "11") (pinfunction "11_11") (pintype "input"))
      (node (ref "U1") (pin "52") (pinfunction "LINK#_52") (pintype "input"))
    )
    (net (code "21") (name "M_C") (class "Default")
      (node (ref "R13") (pin "2") (pinfunction "2_2") (pintype "input"))
      (node (ref "U7") (pin "34") (pinfunction "PA13_34") (pintype "input"))
    )
    (net (code "22") (name "M_D") (class "Default")
      (node (ref "R12") (pin "2") (pinfunction "2_2") (pintype "input"))
      (node (ref "U7") (pin "37") (pinfunction "PA14_37") (pintype "input"))
    )
    (net (code "23") (name "M_DIR") (class "Default")
      (node (ref "R16") (pin "1") (pinfunction "1_1") (pintype "input"))
      (node (ref "U11") (pin "2") (pinfunction "#RE_2") (pintype "input"))
      (node (ref "U11") (pin "3") (pinfunction "DE_3") (pintype "input"))
      (node (ref "U7") (pin "33") (pinfunction "PA12_33") (pintype "input"))
    )
    (net (code "24") (name "M_IO_PA4") (class "Default")
      (node (ref "H2") (pin "1") (pinfunction "1_1") (pintype "input"))
      (node (ref "U7") (pin "14") (pinfunction "PA4_14") (pintype "input"))
    )
    (net (code "25") (name "M_IO_PA5") (class "Default")
      (node (ref "H2") (pin "3") (pinfunction "3_3") (pintype "input"))
      (node (ref "U7") (pin "15") (pinfunction "PA5_15") (pintype "input"))
    )
    (net (code "26") (name "M_IO_PA6") (class "Default")
      (node (ref "H2") (pin "5") (pinfunction "5_5") (pintype "input"))
      (node (ref "U7") (pin "16") (pinfunction "PA6_16") (pintype "input"))
    )
    (net (code "27") (name "M_IO_PA7") (class "Default")
      (node (ref "H2") (pin "7") (pinfunction "7_7") (pintype "input"))
      (node (ref "U7") (pin "17") (pinfunction "PA7_17") (pintype "input"))
    )
    (net (code "28") (name "M_IO_PB1") (class "Default")
      (node (ref "H2") (pin "2") (pinfunction "2_2") (pintype "input"))
      (node (ref "U7") (pin "19") (pinfunction "PB1_19") (pintype "input"))
    )
    (net (code "29") (name "M_IO_PB2") (class "Default")
      (node (ref "H2") (pin "4") (pinfunction "4_4") (pintype "input"))
      (node (ref "U7") (pin "20") (pinfunction "PB2_20") (pintype "input"))
    )
    (net (code "30") (name "M_IO_PB10") (class "Default")
      (node (ref "H2") (pin "6") (pinfunction "6_6") (pintype "input"))
      (node (ref "U7") (pin "21") (pinfunction "PB10_21") (pintype "input"))
    )
    (net (code "31") (name "M_IO_PB11") (class "Default")
      (node (ref "H2") (pin "8") (pinfunction "8_8") (pintype "input"))
      (node (ref "U7") (pin "22") (pinfunction "PB11_22") (pintype "input"))
    )
    (net (code "32") (name "M_K1") (class "Default")
      (node (ref "U7") (pin "10") (pinfunction "PA0-WKUP_10") (pintype "input"))
      (node (ref "U9") (pin "1") (pinfunction "1B_1") (pintype "input"))
      (node (ref "U9") (pin "2") (pinfunction "2B_2") (pintype "input"))
    )
    (net (code "33") (name "M_K2") (class "Default")
      (node (ref "U7") (pin "11") (pinfunction "PA1_11") (pintype "input"))
      (node (ref "U9") (pin "3") (pinfunction "3B_3") (pintype "input"))
      (node (ref "U9") (pin "4") (pinfunction "4B_4") (pintype "input"))
    )
    (net (code "34") (name "M_K3") (class "Default")
      (node (ref "U7") (pin "12") (pinfunction "PA2_12") (pintype "input"))
      (node (ref "U9") (pin "5") (pinfunction "5B_5") (pintype "input"))
      (node (ref "U9") (pin "6") (pinfunction "6B_6") (pintype "input"))
    )
    (net (code "35") (name "M_K4") (class "Default")
      (node (ref "U7") (pin "13") (pinfunction "PA3_13") (pintype "input"))
      (node (ref "U9") (pin "7") (pinfunction "7B_7") (pintype "input"))
    )
    (net (code "36") (name "M_KC1") (class "Default")
      (node (ref "K1") (pin "2") (pinfunction "2_2") (pintype "input"))
      (node (ref "U9") (pin "15") (pinfunction "2C_15") (pintype "input"))
      (node (ref "U9") (pin "16") (pinfunction "1C_16") (pintype "input"))
    )
    (net (code "37") (name "M_KC2") (class "Default")
      (node (ref "K2") (pin "2") (pinfunction "2_2") (pintype "input"))
      (node (ref "U9") (pin "13") (pinfunction "4C_13") (pintype "input"))
      (node (ref "U9") (pin "14") (pinfunction "3C_14") (pintype "input"))
    )
    (net (code "38") (name "M_KC3") (class "Default")
      (node (ref "K3") (pin "2") (pinfunction "2_2") (pintype "input"))
      (node (ref "U9") (pin "11") (pinfunction "6C_11") (pintype "input"))
      (node (ref "U9") (pin "12") (pinfunction "5C_12") (pintype "input"))
    )
    (net (code "39") (name "M_KC4") (class "Default")
      (node (ref "K4") (pin "2") (pinfunction "2_2") (pintype "input"))
      (node (ref "U9") (pin "10") (pinfunction "7C_10") (pintype "input"))
    )
    (net (code "40") (name "M_RST#") (class "Default")
      (node (ref "C28") (pin "1") (pinfunction "1_1") (pintype "input"))
      (node (ref "R11") (pin "1") (pinfunction "1_1") (pintype "input"))
      (node (ref "U7") (pin "7") (pinfunction "NRST_7") (pintype "input"))
    )
    (net (code "41") (name "M_RXD") (class "Default")
      (node (ref "R18") (pin "2") (pinfunction "2_2") (pintype "input"))
      (node (ref "U11") (pin "1") (pinfunction "RO_1") (pintype "input"))
      (node (ref "U7") (pin "31") (pinfunction "PA10_31") (pintype "input"))
    )
    (net (code "42") (name "M_SCL") (class "Default")
      (node (ref "R15") (pin "2") (pinfunction "2_2") (pintype "input"))
      (node (ref "U10") (pin "6") (pinfunction "SCL_6") (pintype "input"))
      (node (ref "U7") (pin "42") (pinfunction "PB6_42") (pintype "input"))
    )
    (net (code "43") (name "M_SDA") (class "Default")
      (node (ref "R14") (pin "1") (pinfunction "1_1") (pintype "input"))
      (node (ref "U10") (pin "5") (pinfunction "SDA_5") (pintype "input"))
      (node (ref "U7") (pin "43") (pinfunction "PB7_43") (pintype "input"))
    )
    (net (code "44") (name "M_TXD") (class "Default")
      (node (ref "R17") (pin "1") (pinfunction "1_1") (pintype "input"))
      (node (ref "U11") (pin "4") (pinfunction "DI_4") (pintype "input"))
      (node (ref "U7") (pin "30") (pinfunction "PA9_30") (pintype "input"))
    )
    (net (code "45") (name "M_X1") (class "Default")
      (node (ref "C33") (pin "2") (pinfunction "2_2") (pintype "input"))
      (node (ref "U7") (pin "5") (pinfunction "PD0-OSCIN_5") (pintype "input"))
      (node (ref "U8") (pin "2") (pinfunction "2_2") (pintype "input"))
    )
    (net (code "46") (name "M_X2") (class "Default")
      (node (ref "C34") (pin "2") (pinfunction "2_2") (pintype "input"))
      (node (ref "U7") (pin "6") (pinfunction "PD1-OSCOUT_6") (pintype "input"))
      (node (ref "U8") (pin "1") (pinfunction "1_1") (pintype "input"))
    )
    (net (code "47") (name "Net-(H1-Pad1)") (class "Default")
      (node (ref "H1") (pin "1") (pinfunction "1_1") (pintype "input"))
      (node (ref "R12") (pin "1") (pinfunction "1_1") (pintype "input"))
    )
    (net (code "48") (name "Net-(H1-Pad4)") (class "Default")
      (node (ref "H1") (pin "4") (pinfunction "4_4") (pintype "input"))
      (node (ref "R13") (pin "1") (pinfunction "1_1") (pintype "input"))
    )
    (net (code "49") (name "Net-(J2-CHS_GND)") (class "Default")
      (node (ref "J2") (pin "8") (pinfunction "CHS_GND_8") (pintype "input"))
      (node (ref "R2") (pin "1") (pinfunction "1_1") (pintype "input"))
    )
    (net (code "50") (name "Net-(J2-Pad9)") (class "Default")
      (node (ref "J2") (pin "9") (pinfunction "9_9") (pintype "input"))
      (node (ref "R6") (pin "1") (pinfunction "1_1") (pintype "input"))
    )
    (net (code "51") (name "Net-(J2-Pad12)") (class "Default")
      (node (ref "J2") (pin "12") (pinfunction "12_12") (pintype "input"))
      (node (ref "R7") (pin "1") (pinfunction "1_1") (pintype "input"))
    )
    (net (code "52") (name "Net-(U1-RSETE)") (class "Default")
      (node (ref "R4") (pin "1") (pinfunction "1_1") (pintype "input"))
      (node (ref "U1") (pin "1") (pinfunction "RSETE_1") (pintype "input"))
    )
    (net (code "53") (name "Net-(U1-TXD)") (class "Default")
      (node (ref "R1") (pin "1") (pinfunction "1_1") (pintype "input"))
      (node (ref "U1") (pin "58") (pinfunction "TXD_58") (pintype "input"))
    )
    (net (code "54") (name "Net-(U11-A)") (class "Default")
      (node (ref "CN5") (pin "1") (pinfunction "1_1") (pintype "input"))
      (node (ref "R19") (pin "1") (pinfunction "1_1") (pintype "input"))
      (node (ref "R21") (pin "2") (pinfunction "2_2") (pintype "input"))
      (node (ref "U11") (pin "6") (pinfunction "A_6") (pintype "input"))
    )
    (net (code "55") (name "Net-(U11-B)") (class "Default")
      (node (ref "CN5") (pin "2") (pinfunction "2_2") (pintype "input"))
      (node (ref "R20") (pin "2") (pinfunction "2_2") (pintype "input"))
      (node (ref "R21") (pin "1") (pinfunction "1_1") (pintype "input"))
      (node (ref "U11") (pin "7") (pinfunction "B_7") (pintype "input"))
    )
    (net (code "56") (name "PGND") (class "Default")
      (node (ref "J2") (pin "SH1") (pinfunction "SH1_SH1") (pintype "input"))
      (node (ref "J2") (pin "SH2") (pinfunction "SH2_SH2") (pintype "input"))
      (node (ref "TP1") (pin "1") (pinfunction "1_1") (pintype "input"))
    )
    (net (code "57") (name "RXN") (class "Default")
      (node (ref "J2") (pin "6") (pinfunction "RD-_6") (pintype "input"))
      (node (ref "R3") (pin "1") (pinfunction "1_1") (pintype "input"))
      (node (ref "U1") (pin "5") (pinfunction "RXN_5") (pintype "input"))
    )
    (net (code "58") (name "RXP") (class "Default")
      (node (ref "J2") (pin "3") (pinfunction "RD+_3") (pintype "input"))
      (node (ref "R5") (pin "1") (pinfunction "1_1") (pintype "input"))
      (node (ref "U1") (pin "4") (pinfunction "RXP_4") (pintype "input"))
    )
    (net (code "59") (name "SEN_OUT") (class "Default")
      (node (ref "C39") (pin "1") (pinfunction "1_1") (pintype "input"))
      (node (ref "R22") (pin "1") (pinfunction "1_1") (pintype "input"))
      (node (ref "U12") (pin "4") (pinfunction "4_4") (pintype "input"))
      (node (ref "U7") (pin "18") (pinfunction "PB0_18") (pintype "input"))
    )
    (net (code "60") (name "S_CTRL") (class "Default")
      (node (ref "R23") (pin "2") (pinfunction "2_2") (pintype "input"))
      (node (ref "U13") (pin "4") (pinfunction "EN#_4") (pintype "input"))
      (node (ref "U7") (pin "38") (pinfunction "PA15_38") (pintype "input"))
    )
    (net (code "61") (name "TXN") (class "Default")
      (node (ref "J2") (pin "2") (pinfunction "TD-_2") (pintype "input"))
      (node (ref "R8") (pin "1") (pinfunction "1_1") (pintype "input"))
      (node (ref "U1") (pin "8") (pinfunction "TXN_8") (pintype "input"))
    )
    (net (code "62") (name "TXP") (class "Default")
      (node (ref "J2") (pin "1") (pinfunction "TD+_1") (pintype "input"))
      (node (ref "R9") (pin "1") (pinfunction "1_1") (pintype "input"))
      (node (ref "U1") (pin "7") (pinfunction "TXP_7") (pintype "input"))
    )
    (net (code "63") (name "V_HU") (class "Default")
      (node (ref "C40") (pin "2") (pinfunction "2_2") (pintype "input"))
      (node (ref "C42") (pin "2") (pinfunction "2_2") (pintype "input"))
      (node (ref "U12") (pin "1") (pinfunction "1_1") (pintype "input"))
      (node (ref "U13") (pin "1") (pinfunction "VOUT_1") (pintype "input"))
    )
    (net (code "64") (name "XI") (class "Default")
      (node (ref "C16") (pin "2") (pinfunction "2_2") (pintype "input"))
      (node (ref "U1") (pin "10") (pinfunction "XI_10") (pintype "input"))
      (node (ref "X1") (pin "2") (pinfunction "OSC2_2") (pintype "input"))
    )
    (net (code "65") (name "XO") (class "Default")
      (node (ref "C17") (pin "2") (pinfunction "2_2") (pintype "input"))
      (node (ref "U1") (pin "11") (pinfunction "XO_11") (pintype "input"))
      (node (ref "X1") (pin "1") (pinfunction "OSC1_1") (pintype "input"))
    )
    (net (code "66") (name "unconnected-(J2-NC-Pad7)") (class "Default")
      (node (ref "J2") (pin "7") (pinfunction "NC_7") (pintype "input+no_connect"))
    )
    (net (code "67") (name "unconnected-(OLED1-GND-Pad1)") (class "Default")
      (node (ref "OLED1") (pin "1") (pinfunction "GND_1") (pintype "input"))
    )
    (net (code "68") (name "unconnected-(OLED1-SCL-Pad3)") (class "Default")
      (node (ref "OLED1") (pin "3") (pinfunction "SCL_3") (pintype "input"))
    )
    (net (code "69") (name "unconnected-(OLED1-SDA-Pad4)") (class "Default")
      (node (ref "OLED1") (pin "4") (pinfunction "SDA_4") (pintype "input"))
    )
    (net (code "70") (name "unconnected-(OLED1-VCC-Pad2)") (class "Default")
      (node (ref "OLED1") (pin "2") (pinfunction "VCC_2") (pintype "input"))
    )
    (net (code "71") (name "unconnected-(U1-GPIO0-Pad22)") (class "Default")
      (node (ref "U1") (pin "22") (pinfunction "GPIO0_22") (pintype "input+no_connect"))
    )
    (net (code "72") (name "unconnected-(U1-GPIO1-Pad23)") (class "Default")
      (node (ref "U1") (pin "23") (pinfunction "GPIO1_23") (pintype "input+no_connect"))
    )
    (net (code "73") (name "unconnected-(U1-GPIO2-Pad24)") (class "Default")
      (node (ref "U1") (pin "24") (pinfunction "GPIO2_24") (pintype "input+no_connect"))
    )
    (net (code "74") (name "unconnected-(U1-GPIO4-Pad32)") (class "Default")
      (node (ref "U1") (pin "32") (pinfunction "GPIO4_32") (pintype "input+no_connect"))
    )
    (net (code "75") (name "unconnected-(U1-GPIO5-Pad33)") (class "Default")
      (node (ref "U1") (pin "33") (pinfunction "GPIO5_33") (pintype "input+no_connect"))
    )
    (net (code "76") (name "unconnected-(U1-GPIO6-Pad34)") (class "Default")
      (node (ref "U1") (pin "34") (pinfunction "GPIO6_34") (pintype "input+no_connect"))
    )
    (net (code "77") (name "unconnected-(U1-GPIO7-Pad35)") (class "Default")
      (node (ref "U1") (pin "35") (pinfunction "GPIO7_35") (pintype "input+no_connect"))
    )
    (net (code "78") (name "unconnected-(U1-NC-Pad14)") (class "Default")
      (node (ref "U1") (pin "14") (pinfunction "NC_14") (pintype "input+no_connect"))
    )
    (net (code "79") (name "unconnected-(U1-NC-Pad15)") (class "Default")
      (node (ref "U1") (pin "15") (pinfunction "NC_15") (pintype "input+no_connect"))
    )
    (net (code "80") (name "unconnected-(U1-NC-Pad16)") (class "Default")
      (node (ref "U1") (pin "16") (pinfunction "NC_16") (pintype "input+no_connect"))
    )
    (net (code "81") (name "unconnected-(U1-NC-Pad30)") (class "Default")
      (node (ref "U1") (pin "30") (pinfunction "NC_30") (pintype "input+no_connect"))
    )
    (net (code "82") (name "unconnected-(U1-NC-Pad31)") (class "Default")
      (node (ref "U1") (pin "31") (pinfunction "NC_31") (pintype "input+no_connect"))
    )
    (net (code "83") (name "unconnected-(U1-NC-Pad38)") (class "Default")
      (node (ref "U1") (pin "38") (pinfunction "NC_38") (pintype "input+no_connect"))
    )
    (net (code "84") (name "unconnected-(U1-NC-Pad39)") (class "Default")
      (node (ref "U1") (pin "39") (pinfunction "NC_39") (pintype "input+no_connect"))
    )
    (net (code "85") (name "unconnected-(U1-NC-Pad46)") (class "Default")
      (node (ref "U1") (pin "46") (pinfunction "NC_46") (pintype "input+no_connect"))
    )
    (net (code "86") (name "unconnected-(U1-NC-Pad47)") (class "Default")
      (node (ref "U1") (pin "47") (pinfunction "NC_47") (pintype "input+no_connect"))
    )
    (net (code "87") (name "unconnected-(U1-NC-Pad50)") (class "Default")
      (node (ref "U1") (pin "50") (pinfunction "NC_50") (pintype "input+no_connect"))
    )
    (net (code "88") (name "unconnected-(U1-NC-Pad51)") (class "Default")
      (node (ref "U1") (pin "51") (pinfunction "NC_51") (pintype "input+no_connect"))
    )
    (net (code "89") (name "unconnected-(U1-NC-Pad53)") (class "Default")
      (node (ref "U1") (pin "53") (pinfunction "NC_53") (pintype "input+no_connect"))
    )
    (net (code "90") (name "unconnected-(U1-NC-Pad55)") (class "Default")
      (node (ref "U1") (pin "55") (pinfunction "NC_55") (pintype "input+no_connect"))
    )
    (net (code "91") (name "unconnected-(U1-NC-Pad56)") (class "Default")
      (node (ref "U1") (pin "56") (pinfunction "NC_56") (pintype "input+no_connect"))
    )
    (net (code "92") (name "unconnected-(U1-RDY#GPIO3-Pad25)") (class "Default")
      (node (ref "U1") (pin "25") (pinfunction "RDY#GPIO3_25") (pintype "input+no_connect"))
    )
    (net (code "93") (name "unconnected-(U1-RST-Pad26)") (class "Default")
      (node (ref "U1") (pin "26") (pinfunction "RST_26") (pintype "input+no_connect"))
    )
    (net (code "94") (name "unconnected-(U1-RXD-Pad57)") (class "Default")
      (node (ref "U1") (pin "57") (pinfunction "RXD_57") (pintype "input+no_connect"))
    )
    (net (code "95") (name "unconnected-(U1-SEL-Pad27)") (class "Default")
      (node (ref "U1") (pin "27") (pinfunction "SEL_27") (pintype "input+no_connect"))
    )
    (net (code "96") (name "unconnected-(U7-PB3-Pad39)") (class "Default")
      (node (ref "U7") (pin "39") (pinfunction "PB3_39") (pintype "input+no_connect"))
    )
    (net (code "97") (name "unconnected-(U7-PB4-Pad40)") (class "Default")
      (node (ref "U7") (pin "40") (pinfunction "PB4_40") (pintype "input+no_connect"))
    )
    (net (code "98") (name "unconnected-(U7-PB5-Pad41)") (class "Default")
      (node (ref "U7") (pin "41") (pinfunction "PB5_41") (pintype "input+no_connect"))
    )
    (net (code "99") (name "unconnected-(U7-PB8-Pad45)") (class "Default")
      (node (ref "U7") (pin "45") (pinfunction "PB8_45") (pintype "input+no_connect"))
    )
    (net (code "100") (name "unconnected-(U7-PB9-Pad46)") (class "Default")
      (node (ref "U7") (pin "46") (pinfunction "PB9_46") (pintype "input+no_connect"))
    )
    (net (code "101") (name "unconnected-(U7-PC13-TAMPER-RTC-Pad2)") (class "Default")
      (node (ref "U7") (pin "2") (pinfunction "PC13-TAMPER-RTC_2") (pintype "input+no_connect"))
    )
    (net (code "102") (name "unconnected-(U7-PC14-OSC32IN-Pad3)") (class "Default")
      (node (ref "U7") (pin "3") (pinfunction "PC14-OSC32IN_3") (pintype "input+no_connect"))
    )
    (net (code "103") (name "unconnected-(U7-PC15-OSC32OUT-Pad4)") (class "Default")
      (node (ref "U7") (pin "4") (pinfunction "PC15-OSC32OUT_4") (pintype "input+no_connect"))
    )
    (net (code "104") (name "unconnected-(U13-FAULT-Pad5)") (class "Default")
      (node (ref "U13") (pin "5") (pinfunction "FAULT_5") (pintype "input+no_connect"))
    )
  )
)
